# v2-DCSupplyHub-outputs.net
KiCad netlist of a schematic drawn in Altium Designer
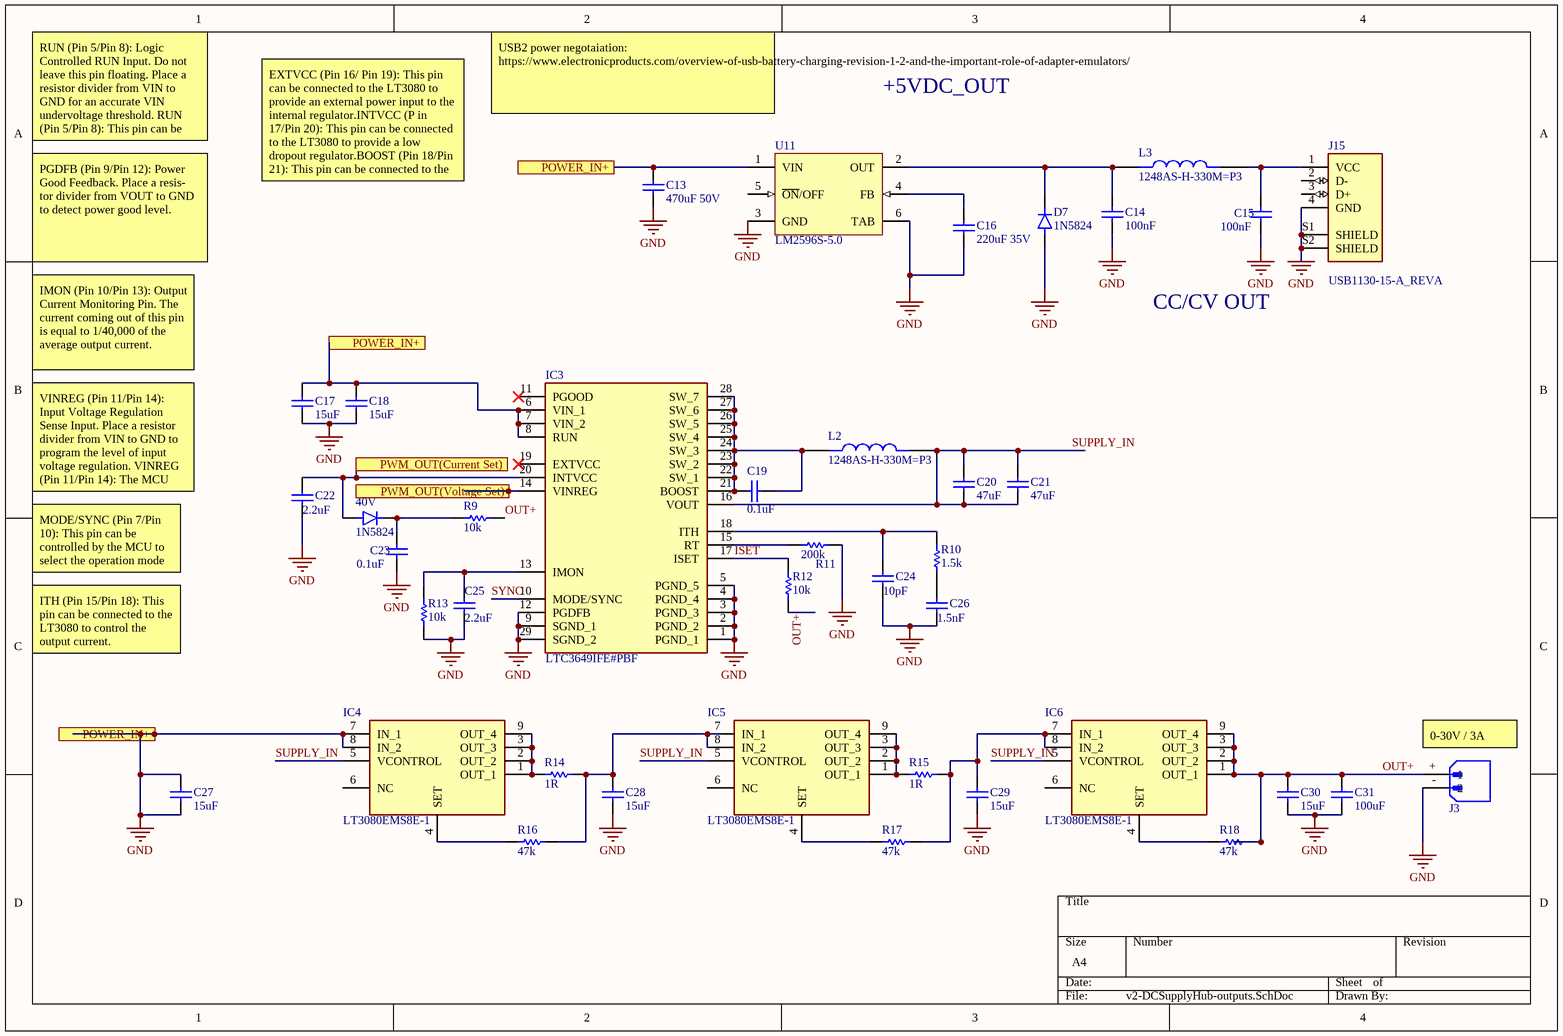
[diagram p0: v2-DCSupplyHub-outputs.SchDoc]

(export (version "E")
  (design (tool "Eeschema 10.0.6"))
  (components
    (comp (ref "40V")
      (value "1N5824")
      (footprint "DIOAD1898W129L762D1143")
      (description "Diode Schottky 30V 5A Through Hole Axial")
      (fields (field (name "MF") "Microsemi Corporation"))
      (libsource (lib "cc cv power supply") (part "1N5824"))
    )
    (comp (ref "C13")
      (value "Cap")
      (footprint "CAPC3216X110N")
      (description "Capacitor")
      (fields (field (name "ALTIUM_UNNAMED_1") "470uF 50V") (field (name "PUBLISHER") "Altium Limited"))
      (libsource (lib "cc cv power supply") (part "Cap"))
    )
    (comp (ref "C14")
      (value "100nF")
      (footprint "CAPC3216X110N")
      (description "Capacitor")
      (fields (field (name "Comment") "Cap") (field (name "PUBLISHER") "Altium Limited"))
      (libsource (lib "cc cv power supply") (part "Cap"))
    )
    (comp (ref "C15")
      (value "100nF")
      (footprint "CAPC3216X110N")
      (description "Capacitor")
      (fields (field (name "Comment") "Cap") (field (name "PUBLISHER") "Altium Limited"))
      (libsource (lib "cc cv power supply") (part "Cap"))
    )
    (comp (ref "C16")
      (value "Cap")
      (footprint "CAPC3216X110N")
      (description "Capacitor")
      (fields (field (name "ALTIUM_UNNAMED_1") "220uF 35V") (field (name "PUBLISHER") "Altium Limited"))
      (libsource (lib "cc cv power supply") (part "Cap"))
    )
    (comp (ref "C17")
      (value "15uF")
      (footprint "CAPC3216X110N")
      (description "Capacitor")
      (fields (field (name "Comment") "Cap") (field (name "PUBLISHER") "Altium Limited"))
      (libsource (lib "cc cv power supply") (part "Cap"))
    )
    (comp (ref "C18")
      (value "15uF")
      (footprint "CAPC3216X110N")
      (description "Capacitor")
      (fields (field (name "Comment") "Cap") (field (name "PUBLISHER") "Altium Limited"))
      (libsource (lib "cc cv power supply") (part "Cap"))
    )
    (comp (ref "C19")
      (value "0.1uF")
      (footprint "CAPC3216X110N")
      (description "Capacitor")
      (fields (field (name "Comment") "Cap") (field (name "PUBLISHER") "Altium Limited"))
      (libsource (lib "cc cv power supply") (part "Cap"))
    )
    (comp (ref "C20")
      (value "47uF")
      (footprint "CAPC3216X110N")
      (description "Capacitor")
      (fields (field (name "Comment") "Cap") (field (name "PUBLISHER") "Altium Limited"))
      (libsource (lib "cc cv power supply") (part "Cap"))
    )
    (comp (ref "C21")
      (value "47uF")
      (footprint "CAPC3216X110N")
      (description "Capacitor")
      (fields (field (name "Comment") "Cap") (field (name "PUBLISHER") "Altium Limited"))
      (libsource (lib "cc cv power supply") (part "Cap"))
    )
    (comp (ref "C22")
      (value "2.2uF")
      (footprint "CAPC3216X110N")
      (description "Capacitor")
      (fields (field (name "Comment") "Cap") (field (name "PUBLISHER") "Altium Limited"))
      (libsource (lib "cc cv power supply") (part "Cap"))
    )
    (comp (ref "C23")
      (value "0.1uF")
      (footprint "CAPC3216X110N")
      (description "Capacitor")
      (fields (field (name "Comment") "Cap") (field (name "PUBLISHER") "Altium Limited"))
      (libsource (lib "cc cv power supply") (part "Cap"))
    )
    (comp (ref "C24")
      (value "10pF")
      (footprint "CAPC3216X110N")
      (description "Capacitor")
      (fields (field (name "Comment") "Cap") (field (name "PUBLISHER") "Altium Limited"))
      (libsource (lib "cc cv power supply") (part "Cap"))
    )
    (comp (ref "C25")
      (value "2.2uF")
      (footprint "CAPC3216X110N")
      (description "Capacitor")
      (fields (field (name "Comment") "Cap") (field (name "PUBLISHER") "Altium Limited"))
      (libsource (lib "cc cv power supply") (part "Cap"))
    )
    (comp (ref "C26")
      (value "1.5nF")
      (footprint "CAPC3216X110N")
      (description "Capacitor")
      (fields (field (name "Comment") "Cap") (field (name "PUBLISHER") "Altium Limited"))
      (libsource (lib "cc cv power supply") (part "Cap"))
    )
    (comp (ref "C27")
      (value "15uF")
      (footprint "CAPC3216X110N")
      (description "Capacitor")
      (fields (field (name "Comment") "Cap") (field (name "PUBLISHER") "Altium Limited"))
      (libsource (lib "cc cv power supply") (part "Cap"))
    )
    (comp (ref "C28")
      (value "15uF")
      (footprint "CAPC3216X110N")
      (description "Capacitor")
      (fields (field (name "Comment") "Cap") (field (name "PUBLISHER") "Altium Limited"))
      (libsource (lib "cc cv power supply") (part "Cap"))
    )
    (comp (ref "C29")
      (value "15uF")
      (footprint "CAPC3216X110N")
      (description "Capacitor")
      (fields (field (name "Comment") "Cap") (field (name "PUBLISHER") "Altium Limited"))
      (libsource (lib "cc cv power supply") (part "Cap"))
    )
    (comp (ref "C30")
      (value "15uF")
      (footprint "CAPC3216X110N")
      (description "Capacitor")
      (fields (field (name "Comment") "Cap") (field (name "PUBLISHER") "Altium Limited"))
      (libsource (lib "cc cv power supply") (part "Cap"))
    )
    (comp (ref "C31")
      (value "100uF")
      (footprint "CAPC3216X110N")
      (description "Capacitor")
      (fields (field (name "Comment") "Cap") (field (name "PUBLISHER") "Altium Limited"))
      (libsource (lib "cc cv power supply") (part "Cap"))
    )
    (comp (ref "D7")
      (value "1N5824")
      (footprint "DIOAD1898W129L762D1143")
      (description "Diode Schottky 30V 5A Through Hole Axial")
      (fields (field (name "MF") "Microsemi Corporation"))
      (libsource (lib "cc cv power supply") (part "1N5824"))
    )
    (comp (ref "IC3")
      (value "LTC3649IFE#PBF")
      (footprint "SOP65P640X120-29N")
      (description "LINEAR TECHNOLOGY - LTC3649IFE#PBF - DC/DC CONV, SYNC BUCK, 1MHZ, TSSOP-28")
      (fields (field (name "MOUSER PART NUMBER") "584-LTC3649IFE#PBF"))
      (libsource (lib "DCSupplyHubLib") (part "LTC3649IFE#PBF"))
    )
    (comp (ref "IC4")
      (value "LT3080EMS8E-1")
      (footprint "SamacSys:SOP65P490X110-9N")
      (description "Integrated Circuit")
      (libsource (lib "DCSupplyHubLib") (part "LT3080EMS8E-1"))
    )
    (comp (ref "IC5")
      (value "LT3080EMS8E-1")
      (footprint "SamacSys:SOP65P490X110-9N")
      (description "Integrated Circuit")
      (libsource (lib "DCSupplyHubLib") (part "LT3080EMS8E-1"))
    )
    (comp (ref "IC6")
      (value "LT3080EMS8E-1")
      (footprint "SamacSys:SOP65P490X110-9N")
      (description "Integrated Circuit")
      (libsource (lib "DCSupplyHubLib") (part "LT3080EMS8E-1"))
    )
    (comp (ref "J3")
      (value "B2B-XH-A(LF)(SN)")
      (footprint "JST_B2B-XH-A(LF)(SN)")
      (description "Connector Header Through Hole 2 position 0.098 (2.50mm)")
      (fields (field (name "MF") "JST Sales"))
      (libsource (lib "cc cv power supply") (part "B2B-XH-A(LF)(SN)"))
    )
    (comp (ref "J15")
      (value "USB1130-15-A_REVA")
      (footprint "GCT_USB1130-15-A_REVA")
      (fields (field (name "MP") "USB1130-15-A") (field (name "MF") "Global Connector Technology"))
      (libsource (lib "cc cv power supply") (part "USB1130-15-A_REVA"))
    )
    (comp (ref "L2")
      (value "1248AS-H-330M=P3")
      (footprint "IND_1248AS-H-330M=P3")
      (description "Inductor with Inductance: 33uH Tol. +/-20%, Package: 3131 _8080_")
      (fields (field (name "MF") "Murata") (field (name "DIGI-KEY_PART_NUMBER") "490-10797-1-ND"))
      (libsource (lib "cc cv power supply") (part "1248AS-H-330M=P3"))
    )
    (comp (ref "L3")
      (value "1248AS-H-330M=P3")
      (footprint "IND_1248AS-H-330M=P3")
      (description "Inductor with Inductance: 33uH Tol. +/-20%, Package: 3131 _8080_")
      (fields (field (name "MF") "Murata") (field (name "DIGI-KEY_PART_NUMBER") "490-10797-1-ND"))
      (libsource (lib "cc cv power supply") (part "1248AS-H-330M=P3"))
    )
    (comp (ref "R9")
      (value "10k")
      (footprint "RESC3116X60N")
      (description "Resistor")
      (fields (field (name "Comment") "Res1") (field (name "PUBLISHER") "Altium Limited"))
      (libsource (lib "cc cv power supply") (part "Res1"))
    )
    (comp (ref "R10")
      (value "1.5k")
      (footprint "RESC3116X60N")
      (description "Resistor")
      (fields (field (name "Comment") "Res1") (field (name "PUBLISHER") "Altium Limited"))
      (libsource (lib "cc cv power supply") (part "Res1"))
    )
    (comp (ref "R11")
      (value "200k")
      (footprint "RESC3116X60N")
      (description "Resistor")
      (fields (field (name "Comment") "Res1") (field (name "PUBLISHER") "Altium Limited"))
      (libsource (lib "cc cv power supply") (part "Res1"))
    )
    (comp (ref "R12")
      (value "10k")
      (footprint "RESC3116X60N")
      (description "Resistor")
      (fields (field (name "Comment") "Res1") (field (name "PUBLISHER") "Altium Limited"))
      (libsource (lib "cc cv power supply") (part "Res1"))
    )
    (comp (ref "R13")
      (value "10k")
      (footprint "RESC3116X60N")
      (description "Resistor")
      (fields (field (name "Comment") "Res1") (field (name "PUBLISHER") "Altium Limited"))
      (libsource (lib "cc cv power supply") (part "Res1"))
    )
    (comp (ref "R14")
      (value "1R")
      (footprint "RESC3116X60N")
      (description "Resistor")
      (fields (field (name "Comment") "Res1") (field (name "PUBLISHER") "Altium Limited"))
      (libsource (lib "cc cv power supply") (part "Res1"))
    )
    (comp (ref "R15")
      (value "1R")
      (footprint "RESC3116X60N")
      (description "Resistor")
      (fields (field (name "Comment") "Res1") (field (name "PUBLISHER") "Altium Limited"))
      (libsource (lib "cc cv power supply") (part "Res1"))
    )
    (comp (ref "R16")
      (value "47k")
      (footprint "RESC3116X60N")
      (description "Resistor")
      (fields (field (name "Comment") "Res1") (field (name "PUBLISHER") "Altium Limited"))
      (libsource (lib "cc cv power supply") (part "Res1"))
    )
    (comp (ref "R17")
      (value "47k")
      (footprint "RESC3116X60N")
      (description "Resistor")
      (fields (field (name "Comment") "Res1") (field (name "PUBLISHER") "Altium Limited"))
      (libsource (lib "cc cv power supply") (part "Res1"))
    )
    (comp (ref "R18")
      (value "47k")
      (footprint "RESC3116X60N")
      (description "Resistor")
      (fields (field (name "Comment") "Res1") (field (name "PUBLISHER") "Altium Limited"))
      (libsource (lib "cc cv power supply") (part "Res1"))
    )
    (comp (ref "U11")
      (value "LM2596S-5.0")
      (footprint "KTT0005B_L")
      (description "SIMPLE SWITCHER® Power Converter 150 KHz 3A Step-Down Voltage Regulator, 5-pin TO-263")
      (fields (field (name "MANUFACTURER") "Texas Instruments"))
      (libsource (lib "Altium Content Vault") (part "PM-REG-LM2575HVS-12"))
    )
  )
  (nets
    (net (code "1") (name "/ISET") (class "Default")
      (node (ref "IC3") (pin "17") (pinfunction "ISET_17") (pintype "passive"))
      (node (ref "R12") (pin "2") (pinfunction "2_2") (pintype "passive"))
    )
    (net (code "2") (name "/OUT+") (class "Default")
      (node (ref "C30") (pin "1") (pinfunction "1_1") (pintype "passive"))
      (node (ref "C31") (pin "1") (pinfunction "1_1") (pintype "passive"))
      (node (ref "IC6") (pin "1") (pinfunction "OUT_1_1") (pintype "passive"))
      (node (ref "IC6") (pin "2") (pinfunction "OUT_2_2") (pintype "passive"))
      (node (ref "IC6") (pin "3") (pinfunction "OUT_3_3") (pintype "passive"))
      (node (ref "IC6") (pin "9") (pinfunction "OUT_4_9") (pintype "passive"))
      (node (ref "J3") (pin "+") (pinfunction "1_+") (pintype "passive"))
      (node (ref "R12") (pin "1") (pinfunction "1_1") (pintype "passive"))
      (node (ref "R18") (pin "2") (pinfunction "2_2") (pintype "passive"))
      (node (ref "R9") (pin "1") (pinfunction "1_1") (pintype "passive"))
    )
    (net (code "3") (name "/PWM_OUT(Current Set)") (class "Default")
      (node (ref "40V") (pin "A") (pinfunction "A_A") (pintype "passive"))
      (node (ref "C22") (pin "1") (pinfunction "1_1") (pintype "passive"))
      (node (ref "IC3") (pin "20") (pinfunction "INTVCC_20") (pintype "passive"))
    )
    (net (code "4") (name "/PWM_OUT(Voltage Set)") (class "Default")
      (node (ref "IC3") (pin "14") (pinfunction "VINREG_14") (pintype "passive"))
    )
    (net (code "5") (name "/SUPPLY_IN") (class "Default")
      (node (ref "C20") (pin "1") (pinfunction "1_1") (pintype "passive"))
      (node (ref "C20") (pin "2") (pinfunction "2_2") (pintype "passive"))
      (node (ref "C21") (pin "1") (pinfunction "1_1") (pintype "passive"))
      (node (ref "C21") (pin "2") (pinfunction "2_2") (pintype "passive"))
      (node (ref "IC3") (pin "16") (pinfunction "VOUT_16") (pintype "passive"))
      (node (ref "IC4") (pin "5") (pinfunction "VCONTROL_5") (pintype "passive"))
      (node (ref "IC5") (pin "5") (pinfunction "VCONTROL_5") (pintype "passive"))
      (node (ref "IC6") (pin "5") (pinfunction "VCONTROL_5") (pintype "passive"))
      (node (ref "L2") (pin "2") (pinfunction "2_2") (pintype "passive"))
    )
    (net (code "6") (name "/SYNC") (class "Default")
      (node (ref "IC3") (pin "10") (pinfunction "MODE/SYNC_10") (pintype "passive"))
    )
    (net (code "7") (name "GND") (class "Default")
      (node (ref "C13") (pin "1") (pinfunction "1_1") (pintype "passive"))
      (node (ref "C13") (pin "2") (pinfunction "2_2") (pintype "passive"))
      (node (ref "C14") (pin "2") (pinfunction "2_2") (pintype "passive"))
      (node (ref "C15") (pin "2") (pinfunction "2_2") (pintype "passive"))
      (node (ref "C16") (pin "1") (pinfunction "1_1") (pintype "passive"))
      (node (ref "C17") (pin "1") (pinfunction "1_1") (pintype "passive"))
      (node (ref "C17") (pin "2") (pinfunction "2_2") (pintype "passive"))
      (node (ref "C18") (pin "1") (pinfunction "1_1") (pintype "passive"))
      (node (ref "C18") (pin "2") (pinfunction "2_2") (pintype "passive"))
      (node (ref "C22") (pin "2") (pinfunction "2_2") (pintype "passive"))
      (node (ref "C23") (pin "2") (pinfunction "2_2") (pintype "passive"))
      (node (ref "C24") (pin "2") (pinfunction "2_2") (pintype "passive"))
      (node (ref "C25") (pin "1") (pinfunction "1_1") (pintype "passive"))
      (node (ref "C26") (pin "2") (pinfunction "2_2") (pintype "passive"))
      (node (ref "C27") (pin "1") (pinfunction "1_1") (pintype "passive"))
      (node (ref "C27") (pin "2") (pinfunction "2_2") (pintype "passive"))
      (node (ref "C28") (pin "2") (pinfunction "2_2") (pintype "passive"))
      (node (ref "C29") (pin "2") (pinfunction "2_2") (pintype "passive"))
      (node (ref "C30") (pin "2") (pinfunction "2_2") (pintype "passive"))
      (node (ref "C31") (pin "2") (pinfunction "2_2") (pintype "passive"))
      (node (ref "D7") (pin "A") (pinfunction "A_A") (pintype "passive"))
      (node (ref "IC3") (pin "1") (pinfunction "PGND_1_1") (pintype "passive"))
      (node (ref "IC3") (pin "12") (pinfunction "PGDFB_12") (pintype "passive"))
      (node (ref "IC3") (pin "2") (pinfunction "PGND_2_2") (pintype "passive"))
      (node (ref "IC3") (pin "29") (pinfunction "SGND_2_29") (pintype "passive"))
      (node (ref "IC3") (pin "3") (pinfunction "PGND_3_3") (pintype "passive"))
      (node (ref "IC3") (pin "4") (pinfunction "PGND_4_4") (pintype "passive"))
      (node (ref "IC3") (pin "5") (pinfunction "PGND_5_5") (pintype "passive"))
      (node (ref "IC3") (pin "6") (pinfunction "VIN_1_6") (pintype "passive"))
      (node (ref "IC3") (pin "7") (pinfunction "VIN_2_7") (pintype "passive"))
      (node (ref "IC3") (pin "8") (pinfunction "RUN_8") (pintype "passive"))
      (node (ref "IC3") (pin "9") (pinfunction "SGND_1_9") (pintype "passive"))
      (node (ref "IC4") (pin "7") (pinfunction "IN_1_7") (pintype "passive"))
      (node (ref "IC4") (pin "8") (pinfunction "IN_2_8") (pintype "passive"))
      (node (ref "J15") (pin "4") (pinfunction "GND_4") (pintype "power_in"))
      (node (ref "J15") (pin "S1") (pinfunction "SHIELD_S1") (pintype "passive"))
      (node (ref "J15") (pin "S2") (pinfunction "SHIELD_S2") (pintype "passive"))
      (node (ref "J3") (pin "-") (pinfunction "2_-") (pintype "passive"))
      (node (ref "R11") (pin "1") (pinfunction "1_1") (pintype "passive"))
      (node (ref "R13") (pin "1") (pinfunction "1_1") (pintype "passive"))
      (node (ref "U11") (pin "1") (pinfunction "VIN_1") (pintype "power_in"))
      (node (ref "U11") (pin "3") (pinfunction "GND_3") (pintype "power_in"))
      (node (ref "U11") (pin "6") (pinfunction "TAB_6") (pintype "power_in"))
    )
    (net (code "8") (name "Net-(40V-K)") (class "Default")
      (node (ref "40V") (pin "C") (pinfunction "K_C") (pintype "passive"))
      (node (ref "C23") (pin "1") (pinfunction "1_1") (pintype "passive"))
      (node (ref "R9") (pin "2") (pinfunction "2_2") (pintype "passive"))
    )
    (net (code "9") (name "Net-(C26-Pad1)") (class "Default")
      (node (ref "C26") (pin "1") (pinfunction "1_1") (pintype "passive"))
      (node (ref "R10") (pin "1") (pinfunction "1_1") (pintype "passive"))
    )
    (net (code "10") (name "Net-(D7-K)") (class "Default")
      (node (ref "C14") (pin "1") (pinfunction "1_1") (pintype "passive"))
      (node (ref "D7") (pin "C") (pinfunction "K_C") (pintype "passive"))
      (node (ref "L3") (pin "1") (pinfunction "1_1") (pintype "passive"))
      (node (ref "U11") (pin "2") (pinfunction "OUT_2") (pintype "power_in"))
    )
    (net (code "11") (name "Net-(IC3-BOOST)") (class "Default")
      (node (ref "C19") (pin "1") (pinfunction "1_1") (pintype "passive"))
      (node (ref "C19") (pin "2") (pinfunction "2_2") (pintype "passive"))
      (node (ref "IC3") (pin "21") (pinfunction "BOOST_21") (pintype "passive"))
      (node (ref "IC3") (pin "22") (pinfunction "SW_1_22") (pintype "passive"))
      (node (ref "IC3") (pin "23") (pinfunction "SW_2_23") (pintype "passive"))
      (node (ref "IC3") (pin "24") (pinfunction "SW_3_24") (pintype "passive"))
      (node (ref "IC3") (pin "25") (pinfunction "SW_4_25") (pintype "passive"))
      (node (ref "IC3") (pin "26") (pinfunction "SW_5_26") (pintype "passive"))
      (node (ref "IC3") (pin "27") (pinfunction "SW_6_27") (pintype "passive"))
      (node (ref "IC3") (pin "28") (pinfunction "SW_7_28") (pintype "passive"))
      (node (ref "L2") (pin "1") (pinfunction "1_1") (pintype "passive"))
    )
    (net (code "12") (name "Net-(IC3-IMON)") (class "Default")
      (node (ref "C25") (pin "2") (pinfunction "2_2") (pintype "passive"))
      (node (ref "IC3") (pin "13") (pinfunction "IMON_13") (pintype "passive"))
      (node (ref "R13") (pin "2") (pinfunction "2_2") (pintype "passive"))
    )
    (net (code "13") (name "Net-(IC3-ITH)") (class "Default")
      (node (ref "C24") (pin "1") (pinfunction "1_1") (pintype "passive"))
      (node (ref "IC3") (pin "18") (pinfunction "ITH_18") (pintype "passive"))
      (node (ref "R10") (pin "2") (pinfunction "2_2") (pintype "passive"))
    )
    (net (code "14") (name "Net-(IC3-RT)") (class "Default")
      (node (ref "IC3") (pin "15") (pinfunction "RT_15") (pintype "passive"))
      (node (ref "R11") (pin "2") (pinfunction "2_2") (pintype "passive"))
    )
    (net (code "15") (name "Net-(IC4-OUT_1)") (class "Default")
      (node (ref "IC4") (pin "1") (pinfunction "OUT_1_1") (pintype "passive"))
      (node (ref "IC4") (pin "2") (pinfunction "OUT_2_2") (pintype "passive"))
      (node (ref "IC4") (pin "3") (pinfunction "OUT_3_3") (pintype "passive"))
      (node (ref "IC4") (pin "9") (pinfunction "OUT_4_9") (pintype "passive"))
      (node (ref "R14") (pin "1") (pinfunction "1_1") (pintype "passive"))
    )
    (net (code "16") (name "Net-(IC4-SET)") (class "Default")
      (node (ref "IC4") (pin "4") (pinfunction "SET_4") (pintype "passive"))
      (node (ref "R16") (pin "1") (pinfunction "1_1") (pintype "passive"))
    )
    (net (code "17") (name "Net-(IC5-IN_1)") (class "Default")
      (node (ref "C28") (pin "1") (pinfunction "1_1") (pintype "passive"))
      (node (ref "IC5") (pin "7") (pinfunction "IN_1_7") (pintype "passive"))
      (node (ref "IC5") (pin "8") (pinfunction "IN_2_8") (pintype "passive"))
      (node (ref "R14") (pin "2") (pinfunction "2_2") (pintype "passive"))
      (node (ref "R16") (pin "2") (pinfunction "2_2") (pintype "passive"))
    )
    (net (code "18") (name "Net-(IC5-OUT_1)") (class "Default")
      (node (ref "IC5") (pin "1") (pinfunction "OUT_1_1") (pintype "passive"))
      (node (ref "IC5") (pin "2") (pinfunction "OUT_2_2") (pintype "passive"))
      (node (ref "IC5") (pin "3") (pinfunction "OUT_3_3") (pintype "passive"))
      (node (ref "IC5") (pin "9") (pinfunction "OUT_4_9") (pintype "passive"))
      (node (ref "R15") (pin "1") (pinfunction "1_1") (pintype "passive"))
    )
    (net (code "19") (name "Net-(IC5-SET)") (class "Default")
      (node (ref "IC5") (pin "4") (pinfunction "SET_4") (pintype "passive"))
      (node (ref "R17") (pin "1") (pinfunction "1_1") (pintype "passive"))
    )
    (net (code "20") (name "Net-(IC6-IN_1)") (class "Default")
      (node (ref "C29") (pin "1") (pinfunction "1_1") (pintype "passive"))
      (node (ref "IC6") (pin "7") (pinfunction "IN_1_7") (pintype "passive"))
      (node (ref "IC6") (pin "8") (pinfunction "IN_2_8") (pintype "passive"))
      (node (ref "R15") (pin "2") (pinfunction "2_2") (pintype "passive"))
      (node (ref "R17") (pin "2") (pinfunction "2_2") (pintype "passive"))
    )
    (net (code "21") (name "Net-(IC6-SET)") (class "Default")
      (node (ref "IC6") (pin "4") (pinfunction "SET_4") (pintype "passive"))
      (node (ref "R18") (pin "1") (pinfunction "1_1") (pintype "passive"))
    )
    (net (code "22") (name "Net-(J15-VCC)") (class "Default")
      (node (ref "C15") (pin "1") (pinfunction "1_1") (pintype "passive"))
      (node (ref "J15") (pin "1") (pinfunction "VCC_1") (pintype "power_in"))
      (node (ref "L3") (pin "2") (pinfunction "2_2") (pintype "passive"))
    )
    (net (code "23") (name "Net-(U11-FB)") (class "Default")
      (node (ref "C16") (pin "2") (pinfunction "2_2") (pintype "passive"))
      (node (ref "U11") (pin "4") (pinfunction "FB_4") (pintype "input"))
    )
    (net (code "24") (name "unconnected-(IC3-EXTVCC-Pad19)") (class "Default")
      (node (ref "IC3") (pin "19") (pinfunction "EXTVCC_19") (pintype "passive+no_connect"))
    )
    (net (code "25") (name "unconnected-(IC3-PGOOD-Pad11)") (class "Default")
      (node (ref "IC3") (pin "11") (pinfunction "PGOOD_11") (pintype "passive+no_connect"))
    )
    (net (code "26") (name "unconnected-(IC4-NC-Pad6)") (class "Default")
      (node (ref "IC4") (pin "6") (pinfunction "NC_6") (pintype "passive"))
    )
    (net (code "27") (name "unconnected-(IC5-NC-Pad6)") (class "Default")
      (node (ref "IC5") (pin "6") (pinfunction "NC_6") (pintype "passive"))
    )
    (net (code "28") (name "unconnected-(IC6-NC-Pad6)") (class "Default")
      (node (ref "IC6") (pin "6") (pinfunction "NC_6") (pintype "passive"))
    )
    (net (code "29") (name "unconnected-(J15-D+-Pad3)") (class "Default")
      (node (ref "J15") (pin "3") (pinfunction "D+_3") (pintype "bidirectional"))
    )
    (net (code "30") (name "unconnected-(J15-D--Pad2)") (class "Default")
      (node (ref "J15") (pin "2") (pinfunction "D-_2") (pintype "bidirectional"))
    )
    (net (code "31") (name "unconnected-(U11-~{ON}{slash}OFF-Pad5)") (class "Default")
      (node (ref "U11") (pin "5") (pinfunction "~{ON}/OFF_5") (pintype "input"))
    )
  )
)
